# Peripherals.net
KiCad netlist of a schematic drawn in Altium Designer
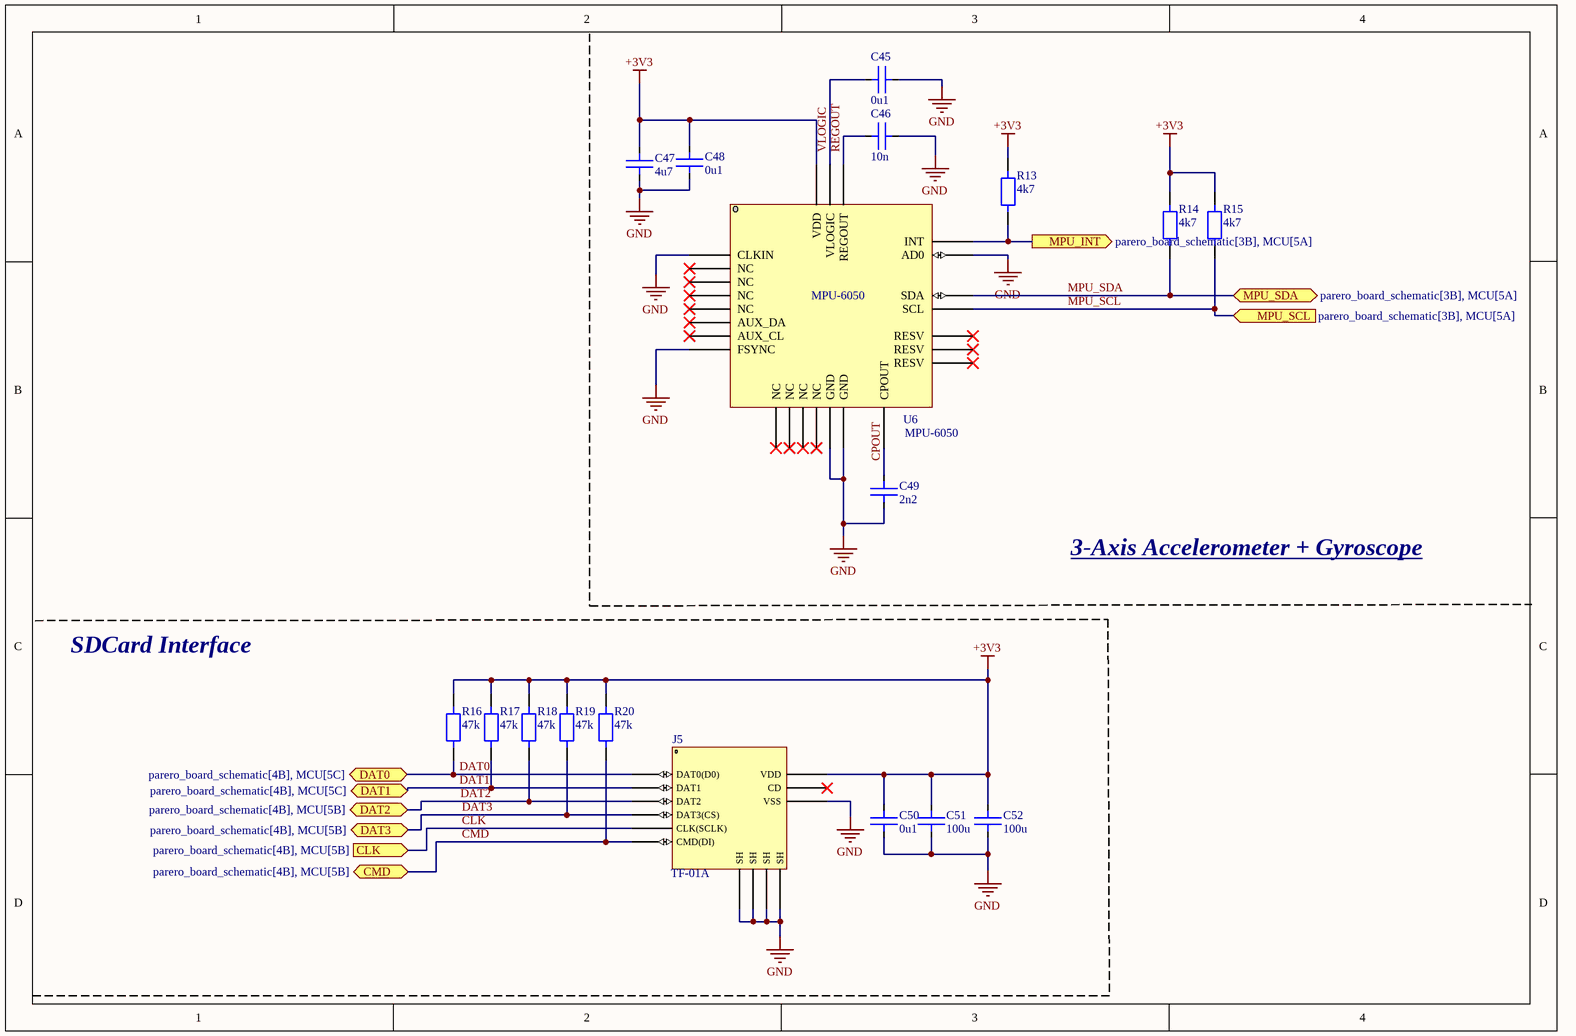
[diagram p0: Peripherals.SchDoc]

(export (version "E")
  (design (tool "Eeschema 10.0.6"))
  (components
    (comp (ref "C45")
      (value "0u1")
      (footprint "CAP_MLCC_0402")
      (description "Multilayer  Ceramic Capacitor")
      (libsource (lib "conics_libs") (part "Cap MLCC 0402"))
    )
    (comp (ref "C46")
      (value "10n")
      (footprint "CAP_MLCC_0402")
      (description "Multilayer  Ceramic Capacitor")
      (libsource (lib "conics_libs") (part "Cap MLCC 0402"))
    )
    (comp (ref "C47")
      (value "4u7")
      (footprint "CAP_MLCC_0603")
      (description "Multilayer  Ceramic Capacitor")
      (libsource (lib "conics_libs") (part "Cap MLCC 0603"))
    )
    (comp (ref "C48")
      (value "0u1")
      (footprint "CAP_MLCC_0402")
      (description "Multilayer  Ceramic Capacitor")
      (libsource (lib "conics_libs") (part "Cap MLCC 0402"))
    )
    (comp (ref "C49")
      (value "2n2")
      (footprint "CAP_MLCC_0402")
      (description "Multilayer  Ceramic Capacitor")
      (libsource (lib "conics_libs") (part "Cap MLCC 0402"))
    )
    (comp (ref "C50")
      (value "0u1")
      (footprint "CAP_MLCC_0402")
      (description "Multilayer  Ceramic Capacitor")
      (libsource (lib "conics_libs") (part "Cap MLCC 0402"))
    )
    (comp (ref "C51")
      (value "100u")
      (footprint "CAP_MLCC_1206")
      (description "Multilayer  Ceramic Capacitor")
      (libsource (lib "conics_libs") (part "Cap MLCC 1206"))
    )
    (comp (ref "C52")
      (value "100u")
      (footprint "CAP_MLCC_1206")
      (description "Multilayer  Ceramic Capacitor")
      (libsource (lib "conics_libs") (part "Cap MLCC 1206"))
    )
    (comp (ref "J5")
      (value "TF-01A")
      (footprint "CONN_CH_SMD_SD_CARD")
      (description "Push-Push 1.85mm Connector and Ejector MicroSD Card (TF Card) SMD PC Card Sockets ROHS")
      (libsource (lib "conics_libs") (part "Connector SD Card CH"))
    )
    (comp (ref "R13")
      (value "4k7")
      (footprint "RES_SMD_0402")
      (description "General Purpose SMD Carbon Resistor")
      (libsource (lib "conics_libs") (part "Resistor 0402"))
    )
    (comp (ref "R14")
      (value "4k7")
      (footprint "RES_SMD_0402")
      (description "General Purpose SMD Carbon Resistor")
      (libsource (lib "conics_libs") (part "Resistor 0402"))
    )
    (comp (ref "R15")
      (value "4k7")
      (footprint "RES_SMD_0402")
      (description "General Purpose SMD Carbon Resistor")
      (libsource (lib "conics_libs") (part "Resistor 0402"))
    )
    (comp (ref "R16")
      (value "47k")
      (footprint "RES_SMD_0402")
      (description "General Purpose SMD Carbon Resistor")
      (libsource (lib "conics_libs") (part "Resistor 0402"))
    )
    (comp (ref "R17")
      (value "47k")
      (footprint "RES_SMD_0402")
      (description "General Purpose SMD Carbon Resistor")
      (libsource (lib "conics_libs") (part "Resistor 0402"))
    )
    (comp (ref "R18")
      (value "47k")
      (footprint "RES_SMD_0402")
      (description "General Purpose SMD Carbon Resistor")
      (libsource (lib "conics_libs") (part "Resistor 0402"))
    )
    (comp (ref "R19")
      (value "47k")
      (footprint "RES_SMD_0402")
      (description "General Purpose SMD Carbon Resistor")
      (libsource (lib "conics_libs") (part "Resistor 0402"))
    )
    (comp (ref "R20")
      (value "47k")
      (footprint "RES_SMD_0402")
      (description "General Purpose SMD Carbon Resistor")
      (libsource (lib "conics_libs") (part "Resistor 0402"))
    )
    (comp (ref "U6")
      (value "MPU-6050")
      (footprint "MPU-6050")
      (description "Accelerometer Gyroscope I2C QFN-24-EP(4x4) Accelerometers ROHS")
      (libsource (lib "conics_libs") (part "Sensor MPU-6050"))
    )
  )
  (nets
    (net (code "1") (name "+3V3") (class "Default")
      (node (ref "C47") (pin "2") (pintype "passive"))
      (node (ref "C48") (pin "2") (pintype "passive"))
      (node (ref "C50") (pin "2") (pintype "passive"))
      (node (ref "C51") (pin "2") (pintype "passive"))
      (node (ref "C52") (pin "2") (pintype "passive"))
      (node (ref "J5") (pin "4") (pinfunction "VDD_4") (pintype "passive"))
      (node (ref "R13") (pin "2") (pintype "passive"))
      (node (ref "R14") (pin "2") (pintype "passive"))
      (node (ref "R15") (pin "2") (pintype "passive"))
      (node (ref "R16") (pin "2") (pintype "passive"))
      (node (ref "R17") (pin "2") (pintype "passive"))
      (node (ref "R18") (pin "2") (pintype "passive"))
      (node (ref "R19") (pin "2") (pintype "passive"))
      (node (ref "R20") (pin "2") (pintype "passive"))
      (node (ref "U6") (pin "13") (pinfunction "VDD_13") (pintype "passive"))
    )
    (net (code "2") (name "/CLK") (class "Default")
      (node (ref "J5") (pin "5") (pinfunction "CLK(SCLK)_5") (pintype "passive"))
    )
    (net (code "3") (name "/CMD") (class "Default")
      (node (ref "J5") (pin "3") (pinfunction "CMD(DI)_3") (pintype "bidirectional"))
      (node (ref "R20") (pin "1") (pintype "passive"))
    )
    (net (code "4") (name "/CPOUT") (class "Default")
      (node (ref "C49") (pin "2") (pintype "passive"))
      (node (ref "U6") (pin "20") (pinfunction "CPOUT_20") (pintype "passive"))
    )
    (net (code "5") (name "/DAT0") (class "Default")
      (node (ref "J5") (pin "7") (pinfunction "DAT0(D0)_7") (pintype "bidirectional"))
      (node (ref "R16") (pin "1") (pintype "passive"))
    )
    (net (code "6") (name "/DAT1") (class "Default")
      (node (ref "J5") (pin "8") (pinfunction "DAT1_8") (pintype "bidirectional"))
      (node (ref "R17") (pin "1") (pintype "passive"))
    )
    (net (code "7") (name "/DAT2") (class "Default")
      (node (ref "J5") (pin "1") (pinfunction "DAT2_1") (pintype "bidirectional"))
      (node (ref "R18") (pin "1") (pintype "passive"))
    )
    (net (code "8") (name "/DAT3") (class "Default")
      (node (ref "J5") (pin "2") (pinfunction "DAT3(CS)_2") (pintype "bidirectional"))
      (node (ref "R19") (pin "1") (pintype "passive"))
    )
    (net (code "9") (name "/MPU_INT") (class "Default")
      (node (ref "R13") (pin "1") (pintype "passive"))
      (node (ref "U6") (pin "12") (pinfunction "INT_12") (pintype "passive"))
    )
    (net (code "10") (name "/MPU_SCL") (class "Default")
      (node (ref "R15") (pin "1") (pintype "passive"))
      (node (ref "U6") (pin "23") (pinfunction "SCL_23") (pintype "passive"))
    )
    (net (code "11") (name "/MPU_SDA") (class "Default")
      (node (ref "R14") (pin "1") (pintype "passive"))
      (node (ref "U6") (pin "24") (pinfunction "SDA_24") (pintype "bidirectional"))
    )
    (net (code "12") (name "/REGOUT") (class "Default")
      (node (ref "C46") (pin "2") (pintype "passive"))
      (node (ref "U6") (pin "10") (pinfunction "REGOUT_10") (pintype "passive"))
    )
    (net (code "13") (name "/VLOGIC") (class "Default")
      (node (ref "C45") (pin "2") (pintype "passive"))
      (node (ref "U6") (pin "8") (pinfunction "VLOGIC_8") (pintype "passive"))
    )
    (net (code "14") (name "GND") (class "Default")
      (node (ref "C45") (pin "1") (pintype "passive"))
      (node (ref "C46") (pin "1") (pintype "passive"))
      (node (ref "C47") (pin "1") (pintype "passive"))
      (node (ref "C48") (pin "1") (pintype "passive"))
      (node (ref "C49") (pin "1") (pintype "passive"))
      (node (ref "C50") (pin "1") (pintype "passive"))
      (node (ref "C51") (pin "1") (pintype "passive"))
      (node (ref "C52") (pin "1") (pintype "passive"))
      (node (ref "J5") (pin "10") (pinfunction "SH_10") (pintype "passive"))
      (node (ref "J5") (pin "11") (pinfunction "SH_11") (pintype "passive"))
      (node (ref "J5") (pin "12") (pinfunction "SH_12") (pintype "passive"))
      (node (ref "J5") (pin "13") (pinfunction "SH_13") (pintype "passive"))
      (node (ref "J5") (pin "6") (pinfunction "VSS_6") (pintype "passive"))
      (node (ref "U6") (pin "1") (pinfunction "CLKIN_1") (pintype "passive"))
      (node (ref "U6") (pin "11") (pinfunction "FSYNC_11") (pintype "passive"))
      (node (ref "U6") (pin "18") (pinfunction "GND_18") (pintype "passive"))
      (node (ref "U6") (pin "25") (pinfunction "GND_25") (pintype "passive"))
      (node (ref "U6") (pin "9") (pinfunction "AD0_9") (pintype "bidirectional"))
    )
    (net (code "15") (name "unconnected-(J5-CD-Pad9)") (class "Default")
      (node (ref "J5") (pin "9") (pinfunction "CD_9") (pintype "passive+no_connect"))
    )
    (net (code "16") (name "unconnected-(U6-AUX_CL-Pad7)") (class "Default")
      (node (ref "U6") (pin "7") (pinfunction "AUX_CL_7") (pintype "passive+no_connect"))
    )
    (net (code "17") (name "unconnected-(U6-AUX_DA-Pad6)") (class "Default")
      (node (ref "U6") (pin "6") (pinfunction "AUX_DA_6") (pintype "passive+no_connect"))
    )
    (net (code "18") (name "unconnected-(U6-NC-Pad2)") (class "Default")
      (node (ref "U6") (pin "2") (pinfunction "NC_2") (pintype "passive+no_connect"))
    )
    (net (code "19") (name "unconnected-(U6-NC-Pad3)") (class "Default")
      (node (ref "U6") (pin "3") (pinfunction "NC_3") (pintype "passive+no_connect"))
    )
    (net (code "20") (name "unconnected-(U6-NC-Pad4)") (class "Default")
      (node (ref "U6") (pin "4") (pinfunction "NC_4") (pintype "passive+no_connect"))
    )
    (net (code "21") (name "unconnected-(U6-NC-Pad5)") (class "Default")
      (node (ref "U6") (pin "5") (pinfunction "NC_5") (pintype "passive+no_connect"))
    )
    (net (code "22") (name "unconnected-(U6-NC-Pad14)") (class "Default")
      (node (ref "U6") (pin "14") (pinfunction "NC_14") (pintype "passive+no_connect"))
    )
    (net (code "23") (name "unconnected-(U6-NC-Pad15)") (class "Default")
      (node (ref "U6") (pin "15") (pinfunction "NC_15") (pintype "passive+no_connect"))
    )
    (net (code "24") (name "unconnected-(U6-NC-Pad16)") (class "Default")
      (node (ref "U6") (pin "16") (pinfunction "NC_16") (pintype "passive+no_connect"))
    )
    (net (code "25") (name "unconnected-(U6-NC-Pad17)") (class "Default")
      (node (ref "U6") (pin "17") (pinfunction "NC_17") (pintype "passive+no_connect"))
    )
    (net (code "26") (name "unconnected-(U6-RESV-Pad19)") (class "Default")
      (node (ref "U6") (pin "19") (pinfunction "RESV_19") (pintype "passive+no_connect"))
    )
    (net (code "27") (name "unconnected-(U6-RESV-Pad21)") (class "Default")
      (node (ref "U6") (pin "21") (pinfunction "RESV_21") (pintype "passive+no_connect"))
    )
    (net (code "28") (name "unconnected-(U6-RESV-Pad22)") (class "Default")
      (node (ref "U6") (pin "22") (pinfunction "RESV_22") (pintype "passive+no_connect"))
    )
  )
)
